# SYS-PS.net
KiCad netlist of a schematic drawn in Altium Designer
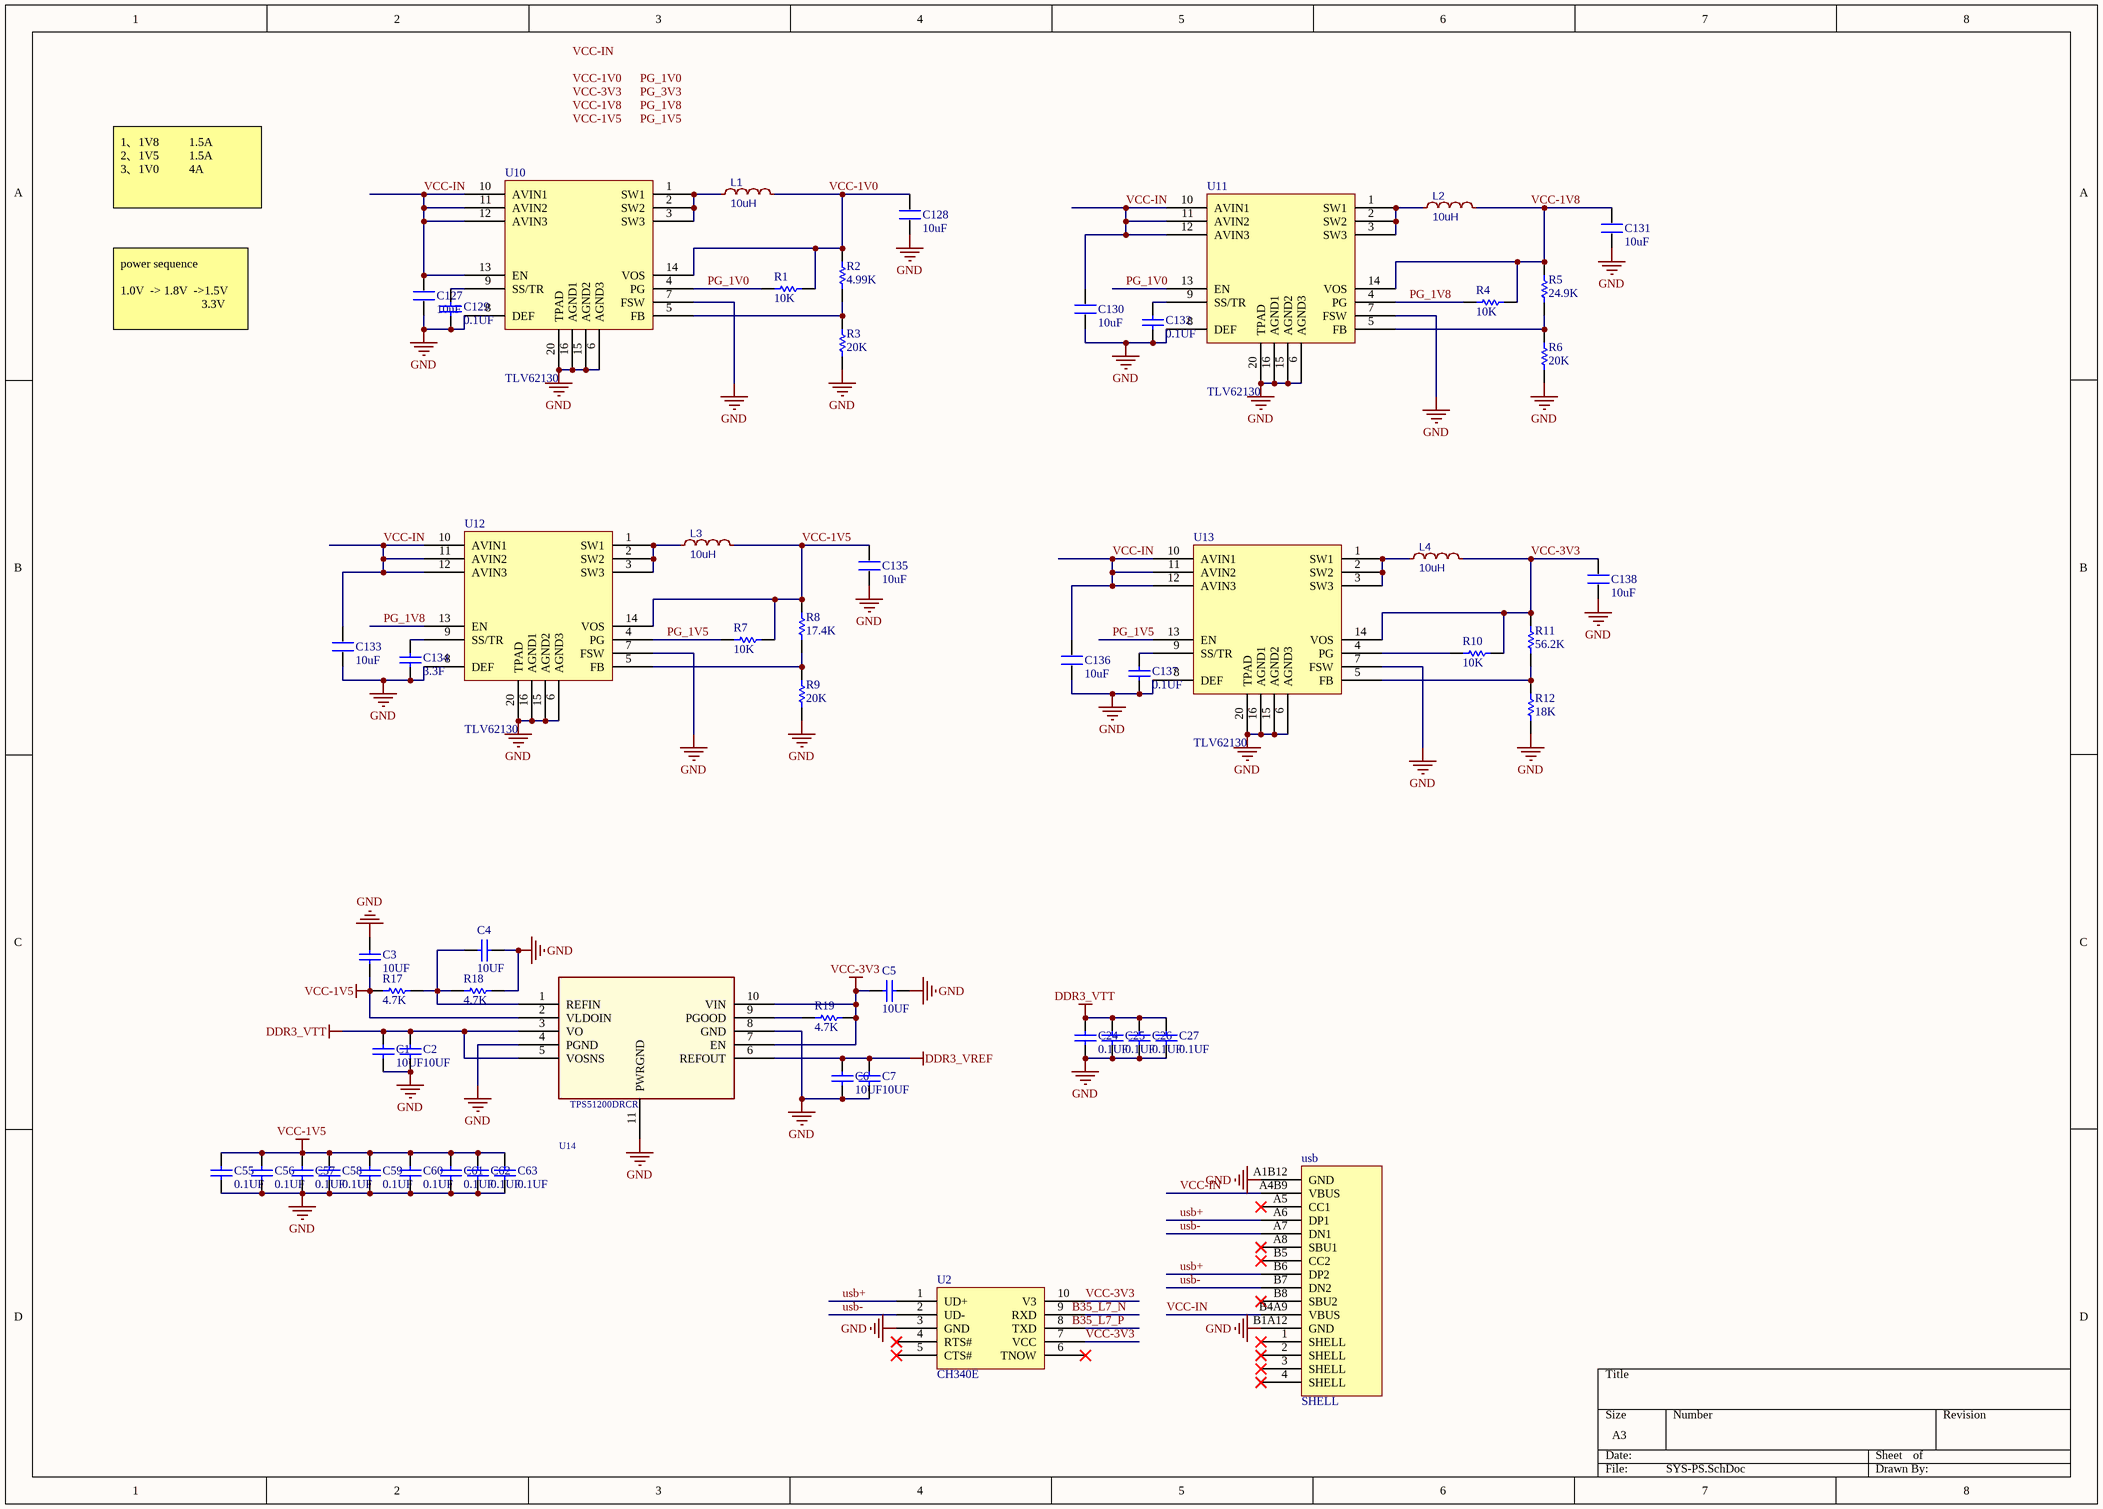
[diagram p0: SYS-PS.SchDoc]

(export (version "E")
  (design (tool "Eeschema 10.0.6"))
  (components
    (comp (ref "C1")
      (value "10UF")
      (footprint "0402")
      (description "Capacitor")
      (fields (field (name "PUBLISHER") "Altium Limited"))
      (libsource (lib "PCB_Project") (part "Cap"))
    )
    (comp (ref "C2")
      (value "10UF")
      (footprint "0402")
      (description "Capacitor")
      (fields (field (name "PUBLISHER") "Altium Limited"))
      (libsource (lib "PCB_Project") (part "Cap"))
    )
    (comp (ref "C3")
      (value "10UF")
      (footprint "0402")
      (description "Capacitor")
      (fields (field (name "PUBLISHER") "Altium Limited"))
      (libsource (lib "PCB_Project") (part "Cap"))
    )
    (comp (ref "C4")
      (value "10UF")
      (footprint "0402")
      (description "Capacitor")
      (fields (field (name "PUBLISHER") "Altium Limited"))
      (libsource (lib "PCB_Project") (part "Cap"))
    )
    (comp (ref "C5")
      (value "10UF")
      (footprint "0402")
      (description "Capacitor")
      (fields (field (name "PUBLISHER") "Altium Limited"))
      (libsource (lib "PCB_Project") (part "Cap"))
    )
    (comp (ref "C6")
      (value "10UF")
      (footprint "0402")
      (description "Capacitor")
      (fields (field (name "PUBLISHER") "Altium Limited"))
      (libsource (lib "PCB_Project") (part "Cap"))
    )
    (comp (ref "C7")
      (value "10UF")
      (footprint "0402")
      (description "Capacitor")
      (fields (field (name "PUBLISHER") "Altium Limited"))
      (libsource (lib "PCB_Project") (part "Cap"))
    )
    (comp (ref "C24")
      (value "0.1UF")
      (footprint "0402")
      (description "Capacitor")
      (fields (field (name "PUBLISHER") "Altium Limited"))
      (libsource (lib "PCB_Project") (part "Cap"))
    )
    (comp (ref "C25")
      (value "0.1UF")
      (footprint "0402")
      (description "Capacitor")
      (fields (field (name "PUBLISHER") "Altium Limited"))
      (libsource (lib "PCB_Project") (part "Cap"))
    )
    (comp (ref "C26")
      (value "0.1UF")
      (footprint "0402")
      (description "Capacitor")
      (fields (field (name "PUBLISHER") "Altium Limited"))
      (libsource (lib "PCB_Project") (part "Cap"))
    )
    (comp (ref "C27")
      (value "0.1UF")
      (footprint "0402")
      (description "Capacitor")
      (fields (field (name "PUBLISHER") "Altium Limited"))
      (libsource (lib "PCB_Project") (part "Cap"))
    )
    (comp (ref "C55")
      (value "0.1UF")
      (footprint "0402")
      (description "Capacitor")
      (fields (field (name "PUBLISHER") "Altium Limited"))
      (libsource (lib "PCB_Project") (part "Cap"))
    )
    (comp (ref "C56")
      (value "0.1UF")
      (footprint "0402")
      (description "Capacitor")
      (fields (field (name "PUBLISHER") "Altium Limited"))
      (libsource (lib "PCB_Project") (part "Cap"))
    )
    (comp (ref "C57")
      (value "0.1UF")
      (footprint "0402")
      (description "Capacitor")
      (fields (field (name "PUBLISHER") "Altium Limited"))
      (libsource (lib "PCB_Project") (part "Cap"))
    )
    (comp (ref "C58")
      (value "0.1UF")
      (footprint "0402")
      (description "Capacitor")
      (fields (field (name "PUBLISHER") "Altium Limited"))
      (libsource (lib "PCB_Project") (part "Cap"))
    )
    (comp (ref "C59")
      (value "0.1UF")
      (footprint "0402")
      (description "Capacitor")
      (fields (field (name "PUBLISHER") "Altium Limited"))
      (libsource (lib "PCB_Project") (part "Cap"))
    )
    (comp (ref "C60")
      (value "0.1UF")
      (footprint "0402")
      (description "Capacitor")
      (fields (field (name "PUBLISHER") "Altium Limited"))
      (libsource (lib "PCB_Project") (part "Cap"))
    )
    (comp (ref "C61")
      (value "0.1UF")
      (footprint "0402")
      (description "Capacitor")
      (fields (field (name "PUBLISHER") "Altium Limited"))
      (libsource (lib "PCB_Project") (part "Cap"))
    )
    (comp (ref "C62")
      (value "0.1UF")
      (footprint "0402")
      (description "Capacitor")
      (fields (field (name "PUBLISHER") "Altium Limited"))
      (libsource (lib "PCB_Project") (part "Cap"))
    )
    (comp (ref "C63")
      (value "0.1UF")
      (footprint "0402")
      (description "Capacitor")
      (fields (field (name "PUBLISHER") "Altium Limited"))
      (libsource (lib "PCB_Project") (part "Cap"))
    )
    (comp (ref "C127") (value "10uF") (footprint "C0805") (libsource (lib "ZYNQ领航者底板") (part "C")))
    (comp (ref "C128") (value "10uF") (footprint "C0805") (libsource (lib "ZYNQ领航者底板") (part "C")))
    (comp (ref "C129")
      (value "0.1UF")
      (footprint "0402")
      (description "Capacitor")
      (fields (field (name "PUBLISHER") "Altium Limited"))
      (libsource (lib "PCB_Project") (part "Cap"))
    )
    (comp (ref "C130") (value "10uF") (footprint "C0805") (libsource (lib "ZYNQ领航者底板") (part "C")))
    (comp (ref "C131") (value "10uF") (footprint "C0805") (libsource (lib "ZYNQ领航者底板") (part "C")))
    (comp (ref "C132")
      (value "0.1UF")
      (footprint "0402")
      (description "Capacitor")
      (fields (field (name "PUBLISHER") "Altium Limited"))
      (libsource (lib "PCB_Project") (part "Cap"))
    )
    (comp (ref "C133") (value "10uF") (footprint "C0805") (libsource (lib "ZYNQ领航者底板") (part "C")))
    (comp (ref "C134")
      (value "3.3F")
      (footprint "0402")
      (description "Capacitor")
      (fields (field (name "PUBLISHER") "Altium Limited"))
      (libsource (lib "PCB_Project") (part "Cap"))
    )
    (comp (ref "C135") (value "10uF") (footprint "C0805") (libsource (lib "ZYNQ领航者底板") (part "C")))
    (comp (ref "C136") (value "10uF") (footprint "C0805") (libsource (lib "ZYNQ领航者底板") (part "C")))
    (comp (ref "C137")
      (value "0.1UF")
      (footprint "0402")
      (description "Capacitor")
      (fields (field (name "PUBLISHER") "Altium Limited"))
      (libsource (lib "PCB_Project") (part "Cap"))
    )
    (comp (ref "C138") (value "10uF") (footprint "C0805") (libsource (lib "ZYNQ领航者底板") (part "C")))
    (comp (ref "L1")
      (value "10uH")
      (footprint "L1008")
      (fields
        (field (name "BOM_SUPPLIER PART") "C370039")
        (field (name "BOM_MANUFACTURER PART") "MPL2520S100MWT")
        (field (name "CONTRIBUTOR") "LCSC")
      )
      (libsource (lib "ZYNQ") (part "10uH"))
    )
    (comp (ref "L2")
      (value "10uH")
      (footprint "L1008")
      (fields
        (field (name "BOM_SUPPLIER PART") "C370039")
        (field (name "BOM_MANUFACTURER PART") "MPL2520S100MWT")
        (field (name "CONTRIBUTOR") "LCSC")
      )
      (libsource (lib "ZYNQ") (part "10uH"))
    )
    (comp (ref "L3")
      (value "10uH")
      (footprint "L1008")
      (fields
        (field (name "BOM_SUPPLIER PART") "C370039")
        (field (name "BOM_MANUFACTURER PART") "MPL2520S100MWT")
        (field (name "CONTRIBUTOR") "LCSC")
      )
      (libsource (lib "ZYNQ") (part "10uH"))
    )
    (comp (ref "L4")
      (value "10uH")
      (footprint "L1008")
      (fields
        (field (name "BOM_SUPPLIER PART") "C370039")
        (field (name "BOM_MANUFACTURER PART") "MPL2520S100MWT")
        (field (name "CONTRIBUTOR") "LCSC")
      )
      (libsource (lib "ZYNQ") (part "10uH"))
    )
    (comp (ref "R1")
      (value "10K")
      (footprint "0402")
      (description "Resistor")
      (fields (field (name "PUBLISHER") "Altium Limited"))
      (libsource (lib "PCB_Project") (part "Res1"))
    )
    (comp (ref "R2")
      (value "4.99K")
      (footprint "0402")
      (description "Resistor")
      (fields (field (name "PUBLISHER") "Altium Limited"))
      (libsource (lib "PCB_Project") (part "Res1"))
    )
    (comp (ref "R3")
      (value "20K")
      (footprint "0402")
      (description "Resistor")
      (fields (field (name "PUBLISHER") "Altium Limited"))
      (libsource (lib "PCB_Project") (part "Res1"))
    )
    (comp (ref "R4")
      (value "10K")
      (footprint "0402")
      (description "Resistor")
      (fields (field (name "PUBLISHER") "Altium Limited"))
      (libsource (lib "PCB_Project") (part "Res1"))
    )
    (comp (ref "R5")
      (value "24.9K")
      (footprint "0402")
      (description "Resistor")
      (fields (field (name "Comment") "4.99K") (field (name "PUBLISHER") "Altium Limited"))
      (libsource (lib "PCB_Project") (part "Res1"))
    )
    (comp (ref "R6")
      (value "20K")
      (footprint "0402")
      (description "Resistor")
      (fields (field (name "Comment") "15K") (field (name "PUBLISHER") "Altium Limited"))
      (libsource (lib "PCB_Project") (part "Res1"))
    )
    (comp (ref "R7")
      (value "10K")
      (footprint "0402")
      (description "Resistor")
      (fields (field (name "PUBLISHER") "Altium Limited"))
      (libsource (lib "PCB_Project") (part "Res1"))
    )
    (comp (ref "R8")
      (value "17.4K")
      (footprint "0402")
      (description "Resistor")
      (fields (field (name "Comment") "4.99K") (field (name "PUBLISHER") "Altium Limited"))
      (libsource (lib "PCB_Project") (part "Res1"))
    )
    (comp (ref "R9")
      (value "20K")
      (footprint "0402")
      (description "Resistor")
      (fields (field (name "Comment") "15K") (field (name "PUBLISHER") "Altium Limited"))
      (libsource (lib "PCB_Project") (part "Res1"))
    )
    (comp (ref "R10")
      (value "10K")
      (footprint "0402")
      (description "Resistor")
      (fields (field (name "PUBLISHER") "Altium Limited"))
      (libsource (lib "PCB_Project") (part "Res1"))
    )
    (comp (ref "R11")
      (value "56.2K")
      (footprint "0402")
      (description "Resistor")
      (fields (field (name "Comment") "4.99K") (field (name "PUBLISHER") "Altium Limited"))
      (libsource (lib "PCB_Project") (part "Res1"))
    )
    (comp (ref "R12")
      (value "18K")
      (footprint "0402")
      (description "Resistor")
      (fields (field (name "Comment") "15K") (field (name "PUBLISHER") "Altium Limited"))
      (libsource (lib "PCB_Project") (part "Res1"))
    )
    (comp (ref "R17")
      (value "4.7K")
      (footprint "0402")
      (description "Resistor")
      (fields (field (name "Comment") "1K") (field (name "PUBLISHER") "Altium Limited"))
      (libsource (lib "PCB_Project") (part "Res1"))
    )
    (comp (ref "R18")
      (value "4.7K")
      (footprint "0402")
      (description "Resistor")
      (fields (field (name "Comment") "1K") (field (name "PUBLISHER") "Altium Limited"))
      (libsource (lib "PCB_Project") (part "Res1"))
    )
    (comp (ref "R19")
      (value "4.7K")
      (footprint "0402")
      (description "Resistor")
      (fields (field (name "Comment") "1K") (field (name "PUBLISHER") "Altium Limited"))
      (libsource (lib "PCB_Project") (part "Res1"))
    )
    (comp (ref "U2") (value "CH340E") (footprint "CH340E") (libsource (lib "PCB_Project") (part "CH340E")))
    (comp (ref "U10") (value "TLV62130") (footprint "TLV62130RGT") (libsource (lib "ZYNQ") (part "TLV62130")))
    (comp (ref "U11") (value "TLV62130") (footprint "TLV62130RGT") (libsource (lib "ZYNQ") (part "TLV62130")))
    (comp (ref "U12") (value "TLV62130") (footprint "TLV62130RGT") (libsource (lib "ZYNQ") (part "TLV62130")))
    (comp (ref "U13") (value "TLV62130") (footprint "TLV62130RGT") (libsource (lib "ZYNQ") (part "TLV62130")))
    (comp (ref "U14")
      (value "TPS51200DRCR")
      (footprint "TPS_QFN10")
      (libsource (lib "ZYNQ_7020") (part "TPS51200DRCR"))
    )
    (comp (ref "usb")
      (value "SHELL")
      (footprint "USB-C-SMD_TYPE-C16PIN_C668624")
      (libsource (lib "PCB_Project") (part "typec_16p"))
    )
  )
  (nets
    (net (code "3") (name "/PG_1V0") (class "Default")
      (node (ref "R1") (pin "1") (pinfunction "1_1") (pintype "passive"))
      (node (ref "U10") (pin "4") (pinfunction "PG_4") (pintype "passive"))
      (node (ref "U11") (pin "13") (pinfunction "EN_13") (pintype "passive"))
    )
    (net (code "4") (name "/PG_1V5") (class "Default")
      (node (ref "R7") (pin "1") (pinfunction "1_1") (pintype "passive"))
      (node (ref "U12") (pin "4") (pinfunction "PG_4") (pintype "passive"))
      (node (ref "U13") (pin "13") (pinfunction "EN_13") (pintype "passive"))
    )
    (net (code "5") (name "/PG_1V8") (class "Default")
      (node (ref "R4") (pin "1") (pinfunction "1_1") (pintype "passive"))
      (node (ref "U11") (pin "4") (pinfunction "PG_4") (pintype "passive"))
      (node (ref "U12") (pin "13") (pinfunction "EN_13") (pintype "passive"))
    )
    (net (code "7") (name "/VCC-1V0") (class "Default")
      (node (ref "C128") (pin "2") (pintype "passive"))
      (node (ref "L1") (pin "2") (pinfunction "2_2") (pintype "passive"))
      (node (ref "R1") (pin "2") (pinfunction "2_2") (pintype "passive"))
      (node (ref "R2") (pin "2") (pinfunction "2_2") (pintype "passive"))
      (node (ref "U10") (pin "14") (pinfunction "VOS_14") (pintype "passive"))
    )
    (net (code "8") (name "/VCC-1V8") (class "Default")
      (node (ref "C131") (pin "2") (pintype "passive"))
      (node (ref "L2") (pin "2") (pinfunction "2_2") (pintype "passive"))
      (node (ref "R4") (pin "2") (pinfunction "2_2") (pintype "passive"))
      (node (ref "R5") (pin "2") (pinfunction "2_2") (pintype "passive"))
      (node (ref "U11") (pin "14") (pinfunction "VOS_14") (pintype "passive"))
    )
    (net (code "9") (name "/VCC-IN") (class "Default")
      (node (ref "C127") (pin "2") (pintype "passive"))
      (node (ref "C130") (pin "2") (pintype "passive"))
      (node (ref "C133") (pin "2") (pintype "passive"))
      (node (ref "C136") (pin "2") (pintype "passive"))
      (node (ref "U10") (pin "10") (pinfunction "AVIN1_10") (pintype "passive"))
      (node (ref "U10") (pin "11") (pinfunction "AVIN2_11") (pintype "passive"))
      (node (ref "U10") (pin "12") (pinfunction "AVIN3_12") (pintype "passive"))
      (node (ref "U10") (pin "13") (pinfunction "EN_13") (pintype "passive"))
      (node (ref "U11") (pin "10") (pinfunction "AVIN1_10") (pintype "passive"))
      (node (ref "U11") (pin "11") (pinfunction "AVIN2_11") (pintype "passive"))
      (node (ref "U11") (pin "12") (pinfunction "AVIN3_12") (pintype "passive"))
      (node (ref "U12") (pin "10") (pinfunction "AVIN1_10") (pintype "passive"))
      (node (ref "U12") (pin "11") (pinfunction "AVIN2_11") (pintype "passive"))
      (node (ref "U12") (pin "12") (pinfunction "AVIN3_12") (pintype "passive"))
      (node (ref "U13") (pin "10") (pinfunction "AVIN1_10") (pintype "passive"))
      (node (ref "U13") (pin "11") (pinfunction "AVIN2_11") (pintype "passive"))
      (node (ref "U13") (pin "12") (pinfunction "AVIN3_12") (pintype "passive"))
      (node (ref "usb") (pin "A4B9") (pinfunction "VBUS_A4B9") (pintype "passive"))
      (node (ref "usb") (pin "B4A9") (pinfunction "VBUS_B4A9") (pintype "passive"))
    )
    (net (code "10") (name "/usb+") (class "Default")
      (node (ref "U2") (pin "1") (pinfunction "UD+_1") (pintype "passive"))
      (node (ref "usb") (pin "A6") (pinfunction "DP1_A6") (pintype "passive"))
      (node (ref "usb") (pin "B6") (pinfunction "DP2_B6") (pintype "passive"))
    )
    (net (code "11") (name "/usb-") (class "Default")
      (node (ref "U2") (pin "2") (pinfunction "UD-_2") (pintype "passive"))
      (node (ref "usb") (pin "A7") (pinfunction "DN1_A7") (pintype "passive"))
      (node (ref "usb") (pin "B7") (pinfunction "DN2_B7") (pintype "passive"))
    )
    (net (code "12") (name "DDR3_VREF") (class "Default")
      (node (ref "C6") (pin "2") (pinfunction "2_2") (pintype "passive"))
      (node (ref "C7") (pin "2") (pinfunction "2_2") (pintype "passive"))
      (node (ref "U14") (pin "6") (pinfunction "REFOUT_6") (pintype "passive"))
    )
    (net (code "13") (name "DDR3_VTT") (class "Default")
      (node (ref "C1") (pin "2") (pinfunction "2_2") (pintype "passive"))
      (node (ref "C2") (pin "2") (pinfunction "2_2") (pintype "passive"))
      (node (ref "C24") (pin "2") (pinfunction "2_2") (pintype "passive"))
      (node (ref "C25") (pin "2") (pinfunction "2_2") (pintype "passive"))
      (node (ref "C26") (pin "2") (pinfunction "2_2") (pintype "passive"))
      (node (ref "C27") (pin "2") (pinfunction "2_2") (pintype "passive"))
      (node (ref "U14") (pin "3") (pinfunction "VO_3") (pintype "passive"))
      (node (ref "U14") (pin "5") (pinfunction "VOSNS_5") (pintype "passive"))
    )
    (net (code "14") (name "GND") (class "Default")
      (node (ref "C1") (pin "1") (pinfunction "1_1") (pintype "passive"))
      (node (ref "C127") (pin "1") (pintype "passive"))
      (node (ref "C128") (pin "1") (pintype "passive"))
      (node (ref "C129") (pin "1") (pinfunction "1_1") (pintype "passive"))
      (node (ref "C130") (pin "1") (pintype "passive"))
      (node (ref "C131") (pin "1") (pintype "passive"))
      (node (ref "C132") (pin "1") (pinfunction "1_1") (pintype "passive"))
      (node (ref "C133") (pin "1") (pintype "passive"))
      (node (ref "C134") (pin "1") (pinfunction "1_1") (pintype "passive"))
      (node (ref "C135") (pin "1") (pintype "passive"))
      (node (ref "C136") (pin "1") (pintype "passive"))
      (node (ref "C137") (pin "1") (pinfunction "1_1") (pintype "passive"))
      (node (ref "C138") (pin "1") (pintype "passive"))
      (node (ref "C2") (pin "1") (pinfunction "1_1") (pintype "passive"))
      (node (ref "C24") (pin "1") (pinfunction "1_1") (pintype "passive"))
      (node (ref "C25") (pin "1") (pinfunction "1_1") (pintype "passive"))
      (node (ref "C26") (pin "1") (pinfunction "1_1") (pintype "passive"))
      (node (ref "C27") (pin "1") (pinfunction "1_1") (pintype "passive"))
      (node (ref "C3") (pin "1") (pinfunction "1_1") (pintype "passive"))
      (node (ref "C4") (pin "2") (pinfunction "2_2") (pintype "passive"))
      (node (ref "C5") (pin "2") (pinfunction "2_2") (pintype "passive"))
      (node (ref "C55") (pin "1") (pinfunction "1_1") (pintype "passive"))
      (node (ref "C56") (pin "1") (pinfunction "1_1") (pintype "passive"))
      (node (ref "C57") (pin "1") (pinfunction "1_1") (pintype "passive"))
      (node (ref "C58") (pin "1") (pinfunction "1_1") (pintype "passive"))
      (node (ref "C59") (pin "1") (pinfunction "1_1") (pintype "passive"))
      (node (ref "C6") (pin "1") (pinfunction "1_1") (pintype "passive"))
      (node (ref "C60") (pin "1") (pinfunction "1_1") (pintype "passive"))
      (node (ref "C61") (pin "1") (pinfunction "1_1") (pintype "passive"))
      (node (ref "C62") (pin "1") (pinfunction "1_1") (pintype "passive"))
      (node (ref "C63") (pin "1") (pinfunction "1_1") (pintype "passive"))
      (node (ref "C7") (pin "1") (pinfunction "1_1") (pintype "passive"))
      (node (ref "R12") (pin "1") (pinfunction "1_1") (pintype "passive"))
      (node (ref "R18") (pin "2") (pinfunction "2_2") (pintype "passive"))
      (node (ref "R3") (pin "1") (pinfunction "1_1") (pintype "passive"))
      (node (ref "R6") (pin "1") (pinfunction "1_1") (pintype "passive"))
      (node (ref "R9") (pin "1") (pinfunction "1_1") (pintype "passive"))
      (node (ref "U10") (pin "15") (pinfunction "AGND2_15") (pintype "passive"))
      (node (ref "U10") (pin "16") (pinfunction "AGND1_16") (pintype "passive"))
      (node (ref "U10") (pin "20") (pinfunction "TPAD_20") (pintype "passive"))
      (node (ref "U10") (pin "6") (pinfunction "AGND3_6") (pintype "passive"))
      (node (ref "U10") (pin "7") (pinfunction "FSW_7") (pintype "passive"))
      (node (ref "U10") (pin "8") (pinfunction "DEF_8") (pintype "passive"))
      (node (ref "U11") (pin "15") (pinfunction "AGND2_15") (pintype "passive"))
      (node (ref "U11") (pin "16") (pinfunction "AGND1_16") (pintype "passive"))
      (node (ref "U11") (pin "20") (pinfunction "TPAD_20") (pintype "passive"))
      (node (ref "U11") (pin "6") (pinfunction "AGND3_6") (pintype "passive"))
      (node (ref "U11") (pin "7") (pinfunction "FSW_7") (pintype "passive"))
      (node (ref "U11") (pin "8") (pinfunction "DEF_8") (pintype "passive"))
      (node (ref "U12") (pin "15") (pinfunction "AGND2_15") (pintype "passive"))
      (node (ref "U12") (pin "16") (pinfunction "AGND1_16") (pintype "passive"))
      (node (ref "U12") (pin "20") (pinfunction "TPAD_20") (pintype "passive"))
      (node (ref "U12") (pin "6") (pinfunction "AGND3_6") (pintype "passive"))
      (node (ref "U12") (pin "7") (pinfunction "FSW_7") (pintype "passive"))
      (node (ref "U12") (pin "8") (pinfunction "DEF_8") (pintype "passive"))
      (node (ref "U13") (pin "15") (pinfunction "AGND2_15") (pintype "passive"))
      (node (ref "U13") (pin "16") (pinfunction "AGND1_16") (pintype "passive"))
      (node (ref "U13") (pin "20") (pinfunction "TPAD_20") (pintype "passive"))
      (node (ref "U13") (pin "6") (pinfunction "AGND3_6") (pintype "passive"))
      (node (ref "U13") (pin "7") (pinfunction "FSW_7") (pintype "passive"))
      (node (ref "U13") (pin "8") (pinfunction "DEF_8") (pintype "passive"))
      (node (ref "U14") (pin "11") (pinfunction "PWRGND_11") (pintype "passive"))
      (node (ref "U14") (pin "4") (pinfunction "PGND_4") (pintype "passive"))
      (node (ref "U14") (pin "8") (pinfunction "GND_8") (pintype "passive"))
      (node (ref "U2") (pin "3") (pinfunction "GND_3") (pintype "passive"))
      (node (ref "usb") (pin "A1B12") (pinfunction "GND_A1B12") (pintype "passive"))
      (node (ref "usb") (pin "B1A12") (pinfunction "GND_B1A12") (pintype "passive"))
    )
    (net (code "15") (name "Net-(U10-FB)") (class "Default")
      (node (ref "R2") (pin "1") (pinfunction "1_1") (pintype "passive"))
      (node (ref "R3") (pin "2") (pinfunction "2_2") (pintype "passive"))
      (node (ref "U10") (pin "5") (pinfunction "FB_5") (pintype "passive"))
    )
    (net (code "16") (name "Net-(U10-SS{slash}TR)") (class "Default")
      (node (ref "C129") (pin "2") (pinfunction "2_2") (pintype "passive"))
      (node (ref "U10") (pin "9") (pinfunction "SS/TR_9") (pintype "passive"))
    )
    (net (code "17") (name "Net-(U10-SW1)") (class "Default")
      (node (ref "L1") (pin "1") (pinfunction "1_1") (pintype "passive"))
      (node (ref "U10") (pin "1") (pinfunction "SW1_1") (pintype "passive"))
      (node (ref "U10") (pin "2") (pinfunction "SW2_2") (pintype "passive"))
      (node (ref "U10") (pin "3") (pinfunction "SW3_3") (pintype "passive"))
    )
    (net (code "18") (name "Net-(U11-FB)") (class "Default")
      (node (ref "R5") (pin "1") (pinfunction "1_1") (pintype "passive"))
      (node (ref "R6") (pin "2") (pinfunction "2_2") (pintype "passive"))
      (node (ref "U11") (pin "5") (pinfunction "FB_5") (pintype "passive"))
    )
    (net (code "19") (name "Net-(U11-SS{slash}TR)") (class "Default")
      (node (ref "C132") (pin "2") (pinfunction "2_2") (pintype "passive"))
      (node (ref "U11") (pin "9") (pinfunction "SS/TR_9") (pintype "passive"))
    )
    (net (code "20") (name "Net-(U11-SW1)") (class "Default")
      (node (ref "L2") (pin "1") (pinfunction "1_1") (pintype "passive"))
      (node (ref "U11") (pin "1") (pinfunction "SW1_1") (pintype "passive"))
      (node (ref "U11") (pin "2") (pinfunction "SW2_2") (pintype "passive"))
      (node (ref "U11") (pin "3") (pinfunction "SW3_3") (pintype "passive"))
    )
    (net (code "21") (name "Net-(U12-FB)") (class "Default")
      (node (ref "R8") (pin "1") (pinfunction "1_1") (pintype "passive"))
      (node (ref "R9") (pin "2") (pinfunction "2_2") (pintype "passive"))
      (node (ref "U12") (pin "5") (pinfunction "FB_5") (pintype "passive"))
    )
    (net (code "22") (name "Net-(U12-SS{slash}TR)") (class "Default")
      (node (ref "C134") (pin "2") (pinfunction "2_2") (pintype "passive"))
      (node (ref "U12") (pin "9") (pinfunction "SS/TR_9") (pintype "passive"))
    )
    (net (code "23") (name "Net-(U12-SW1)") (class "Default")
      (node (ref "L3") (pin "1") (pinfunction "1_1") (pintype "passive"))
      (node (ref "U12") (pin "1") (pinfunction "SW1_1") (pintype "passive"))
      (node (ref "U12") (pin "2") (pinfunction "SW2_2") (pintype "passive"))
      (node (ref "U12") (pin "3") (pinfunction "SW3_3") (pintype "passive"))
    )
    (net (code "24") (name "Net-(U13-FB)") (class "Default")
      (node (ref "R11") (pin "1") (pinfunction "1_1") (pintype "passive"))
      (node (ref "R12") (pin "2") (pinfunction "2_2") (pintype "passive"))
      (node (ref "U13") (pin "5") (pinfunction "FB_5") (pintype "passive"))
    )
    (net (code "25") (name "Net-(U13-PG)") (class "Default")
      (node (ref "R10") (pin "1") (pinfunction "1_1") (pintype "passive"))
      (node (ref "U13") (pin "4") (pinfunction "PG_4") (pintype "passive"))
    )
    (net (code "26") (name "Net-(U13-SS{slash}TR)") (class "Default")
      (node (ref "C137") (pin "2") (pinfunction "2_2") (pintype "passive"))
      (node (ref "U13") (pin "9") (pinfunction "SS/TR_9") (pintype "passive"))
    )
    (net (code "27") (name "Net-(U13-SW1)") (class "Default")
      (node (ref "L4") (pin "1") (pinfunction "1_1") (pintype "passive"))
      (node (ref "U13") (pin "1") (pinfunction "SW1_1") (pintype "passive"))
      (node (ref "U13") (pin "2") (pinfunction "SW2_2") (pintype "passive"))
      (node (ref "U13") (pin "3") (pinfunction "SW3_3") (pintype "passive"))
    )
    (net (code "28") (name "Net-(U14-PGOOD)") (class "Default")
      (node (ref "R19") (pin "1") (pinfunction "1_1") (pintype "passive"))
      (node (ref "U14") (pin "9") (pinfunction "PGOOD_9") (pintype "passive"))
    )
    (net (code "29") (name "Net-(U14-REFIN)") (class "Default")
      (node (ref "C4") (pin "1") (pinfunction "1_1") (pintype "passive"))
      (node (ref "R17") (pin "2") (pinfunction "2_2") (pintype "passive"))
      (node (ref "R18") (pin "1") (pinfunction "1_1") (pintype "passive"))
      (node (ref "U14") (pin "1") (pinfunction "REFIN_1") (pintype "passive"))
    )
    (net (code "30") (name "VCC-1V5") (class "Default")
      (node (ref "C135") (pin "2") (pintype "passive"))
      (node (ref "C3") (pin "2") (pinfunction "2_2") (pintype "passive"))
      (node (ref "C55") (pin "2") (pinfunction "2_2") (pintype "passive"))
      (node (ref "C56") (pin "2") (pinfunction "2_2") (pintype "passive"))
      (node (ref "C57") (pin "2") (pinfunction "2_2") (pintype "passive"))
      (node (ref "C58") (pin "2") (pinfunction "2_2") (pintype "passive"))
      (node (ref "C59") (pin "2") (pinfunction "2_2") (pintype "passive"))
      (node (ref "C60") (pin "2") (pinfunction "2_2") (pintype "passive"))
      (node (ref "C61") (pin "2") (pinfunction "2_2") (pintype "passive"))
      (node (ref "C62") (pin "2") (pinfunction "2_2") (pintype "passive"))
      (node (ref "C63") (pin "2") (pinfunction "2_2") (pintype "passive"))
      (node (ref "L3") (pin "2") (pinfunction "2_2") (pintype "passive"))
      (node (ref "R17") (pin "1") (pinfunction "1_1") (pintype "passive"))
      (node (ref "R7") (pin "2") (pinfunction "2_2") (pintype "passive"))
      (node (ref "R8") (pin "2") (pinfunction "2_2") (pintype "passive"))
      (node (ref "U12") (pin "14") (pinfunction "VOS_14") (pintype "passive"))
      (node (ref "U14") (pin "2") (pinfunction "VLDOIN_2") (pintype "passive"))
    )
    (net (code "31") (name "VCC-3V3") (class "Default")
      (node (ref "C138") (pin "2") (pintype "passive"))
      (node (ref "C5") (pin "1") (pinfunction "1_1") (pintype "passive"))
      (node (ref "L4") (pin "2") (pinfunction "2_2") (pintype "passive"))
      (node (ref "R10") (pin "2") (pinfunction "2_2") (pintype "passive"))
      (node (ref "R11") (pin "2") (pinfunction "2_2") (pintype "passive"))
      (node (ref "R19") (pin "2") (pinfunction "2_2") (pintype "passive"))
      (node (ref "U13") (pin "14") (pinfunction "VOS_14") (pintype "passive"))
      (node (ref "U14") (pin "10") (pinfunction "VIN_10") (pintype "passive"))
      (node (ref "U14") (pin "7") (pinfunction "EN_7") (pintype "passive"))
      (node (ref "U2") (pin "10") (pinfunction "V3_10") (pintype "passive"))
      (node (ref "U2") (pin "7") (pinfunction "VCC_7") (pintype "passive"))
    )
    (net (code "32") (name "unconnected-(U2-CTS#-Pad5)") (class "Default")
      (node (ref "U2") (pin "5") (pinfunction "CTS#_5") (pintype "passive+no_connect"))
    )
    (net (code "33") (name "unconnected-(U2-RTS#-Pad4)") (class "Default")
      (node (ref "U2") (pin "4") (pinfunction "RTS#_4") (pintype "passive+no_connect"))
    )
    (net (code "34") (name "unconnected-(U2-RXD-Pad9)") (class "Default")
      (node (ref "U2") (pin "9") (pinfunction "RXD_9") (pintype "passive"))
    )
    (net (code "35") (name "unconnected-(U2-TNOW-Pad6)") (class "Default")
      (node (ref "U2") (pin "6") (pinfunction "TNOW_6") (pintype "passive+no_connect"))
    )
    (net (code "36") (name "unconnected-(U2-TXD-Pad8)") (class "Default")
      (node (ref "U2") (pin "8") (pinfunction "TXD_8") (pintype "passive"))
    )
    (net (code "37") (name "unconnected-(usb-CC1-PadA5)") (class "Default")
      (node (ref "usb") (pin "A5") (pinfunction "CC1_A5") (pintype "passive+no_connect"))
    )
    (net (code "38") (name "unconnected-(usb-CC2-PadB5)") (class "Default")
      (node (ref "usb") (pin "B5") (pinfunction "CC2_B5") (pintype "passive+no_connect"))
    )
    (net (code "39") (name "unconnected-(usb-SBU1-PadA8)") (class "Default")
      (node (ref "usb") (pin "A8") (pinfunction "SBU1_A8") (pintype "passive+no_connect"))
    )
    (net (code "40") (name "unconnected-(usb-SBU2-PadB8)") (class "Default")
      (node (ref "usb") (pin "B8") (pinfunction "SBU2_B8") (pintype "passive+no_connect"))
    )
    (net (code "41") (name "unconnected-(usb-SHELL-Pad1)") (class "Default")
      (node (ref "usb") (pin "1") (pinfunction "SHELL_1") (pintype "passive+no_connect"))
    )
    (net (code "42") (name "unconnected-(usb-SHELL-Pad2)") (class "Default")
      (node (ref "usb") (pin "2") (pinfunction "SHELL_2") (pintype "passive+no_connect"))
    )
    (net (code "43") (name "unconnected-(usb-SHELL-Pad3)") (class "Default")
      (node (ref "usb") (pin "3") (pinfunction "SHELL_3") (pintype "passive+no_connect"))
    )
    (net (code "44") (name "unconnected-(usb-SHELL-Pad4)") (class "Default")
      (node (ref "usb") (pin "4") (pinfunction "SHELL_4") (pintype "passive+no_connect"))
    )
  )
)
